# 7_07110_016_3.net
KiCad netlist of a schematic drawn in Altium Designer
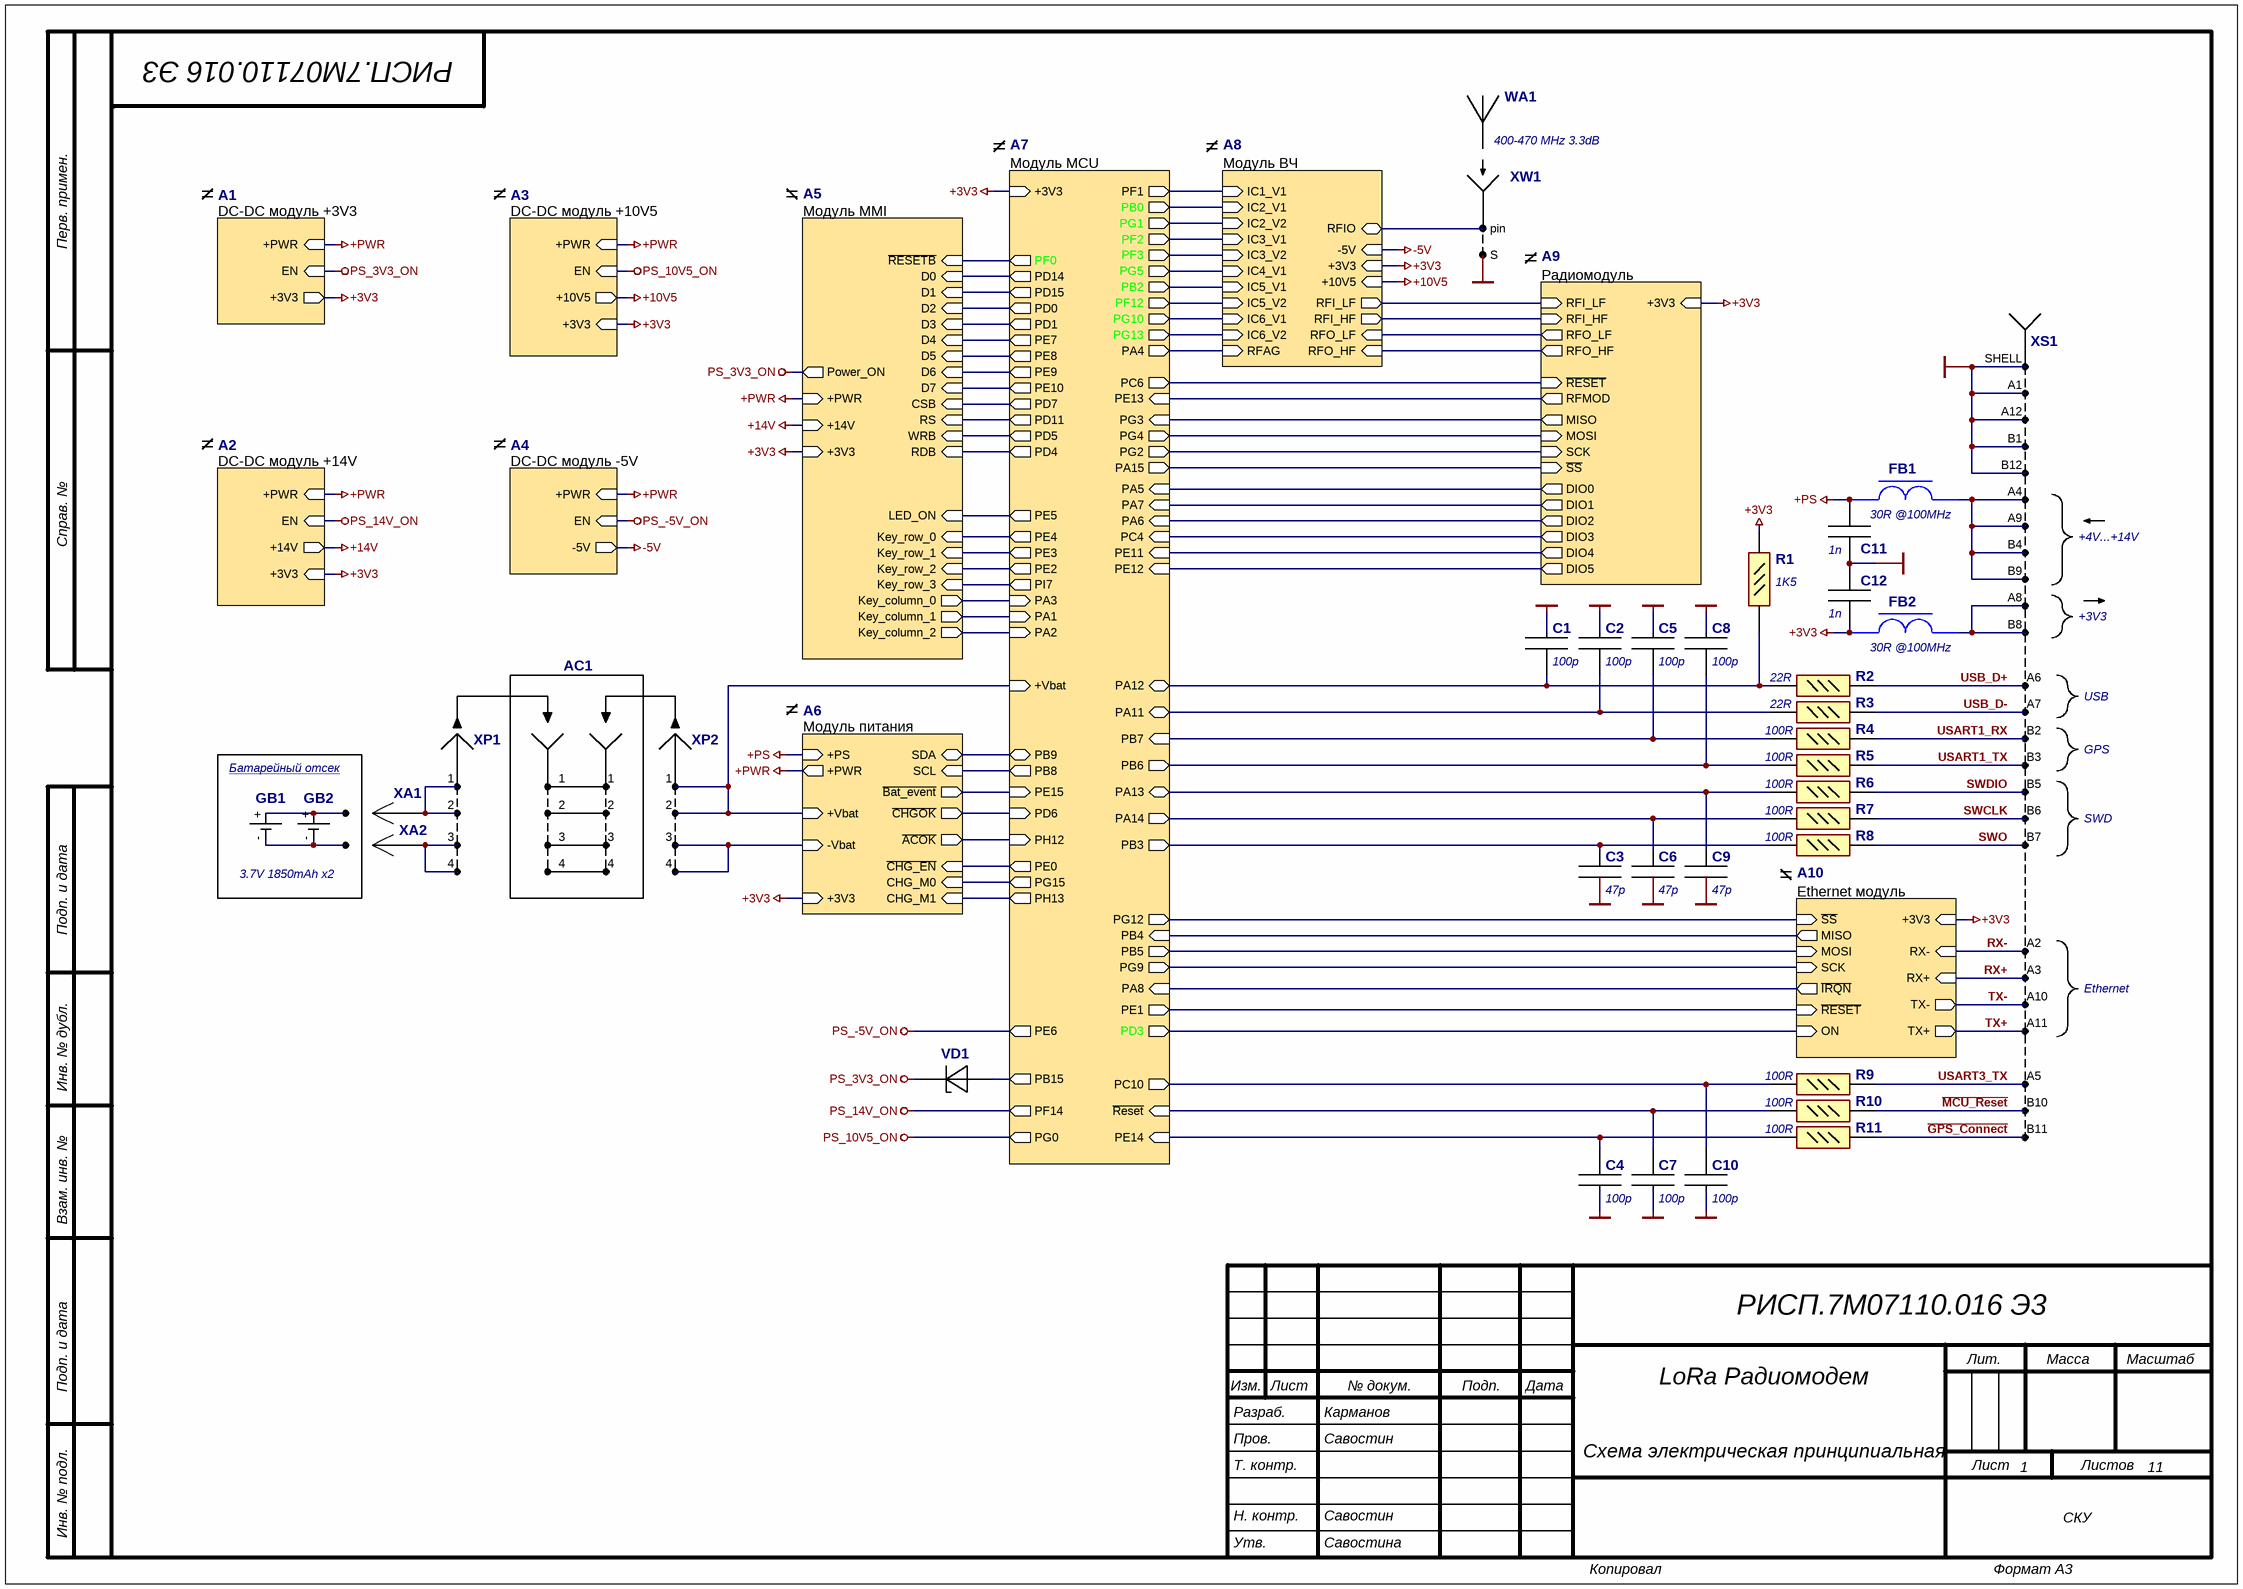
[diagram p0: РИСП.7М07110.016 Э3.SchDoc]

(export (version "E")
  (design (tool "Eeschema 10.0.6"))
  (components
    (comp (ref "AC1")
      (value "0151320401")
      (description "Cable-Assy Picolock 1.5mm Pitch 4 Wire 24AWG 100mm")
      (libsource (lib "Connectors") (part "0151320401"))
    )
    (comp (ref "C1")
      (value "100p")
      (footprint ":CAP0402 100x50x50")
      (description "CAP CER  50V C0G/NP0 0402")
      (fields (field (name "MANUFACTURER_PART_NUMBER") "GCM1555C1H101JA16D"))
      (libsource (lib "Capacitors 0402") (part "GCM1555C1H101JA16D"))
    )
    (comp (ref "C2")
      (value "100p")
      (footprint ":CAP0402 100x50x50")
      (description "CAP CER  50V C0G/NP0 0402")
      (fields (field (name "MANUFACTURER_PART_NUMBER") "GCM1555C1H101JA16D"))
      (libsource (lib "Capacitors 0402") (part "GCM1555C1H101JA16D"))
    )
    (comp (ref "C3")
      (value "47p")
      (footprint ":CAP0402 100x50x50")
      (description "CAP CER  50V C0G/NP0 0402")
      (fields (field (name "MANUFACTURER_PART_NUMBER") "GJM1555C1H470GB01D"))
      (libsource (lib "Capacitors 0402") (part "GJM1555C1H470GB01D"))
    )
    (comp (ref "C4")
      (value "100p")
      (footprint ":CAP0402 100x50x50")
      (description "CAP CER  50V C0G/NP0 0402")
      (fields (field (name "MANUFACTURER_PART_NUMBER") "GCM1555C1H101JA16D"))
      (libsource (lib "Capacitors 0402") (part "GCM1555C1H101JA16D"))
    )
    (comp (ref "C5")
      (value "100p")
      (footprint ":CAP0402 100x50x50")
      (description "CAP CER  50V C0G/NP0 0402")
      (fields (field (name "MANUFACTURER_PART_NUMBER") "GCM1555C1H101JA16D"))
      (libsource (lib "Capacitors 0402") (part "GCM1555C1H101JA16D"))
    )
    (comp (ref "C6")
      (value "47p")
      (footprint ":CAP0402 100x50x50")
      (description "CAP CER  50V C0G/NP0 0402")
      (fields (field (name "MANUFACTURER_PART_NUMBER") "GJM1555C1H470GB01D"))
      (libsource (lib "Capacitors 0402") (part "GJM1555C1H470GB01D"))
    )
    (comp (ref "C7")
      (value "100p")
      (footprint ":CAP0402 100x50x50")
      (description "CAP CER  50V C0G/NP0 0402")
      (fields (field (name "MANUFACTURER_PART_NUMBER") "GCM1555C1H101JA16D"))
      (libsource (lib "Capacitors 0402") (part "GCM1555C1H101JA16D"))
    )
    (comp (ref "C8")
      (value "100p")
      (footprint ":CAP0402 100x50x50")
      (description "CAP CER  50V C0G/NP0 0402")
      (fields (field (name "MANUFACTURER_PART_NUMBER") "GCM1555C1H101JA16D"))
      (libsource (lib "Capacitors 0402") (part "GCM1555C1H101JA16D"))
    )
    (comp (ref "C9")
      (value "47p")
      (footprint ":CAP0402 100x50x50")
      (description "CAP CER  50V C0G/NP0 0402")
      (fields (field (name "MANUFACTURER_PART_NUMBER") "GJM1555C1H470GB01D"))
      (libsource (lib "Capacitors 0402") (part "GJM1555C1H470GB01D"))
    )
    (comp (ref "C10")
      (value "100p")
      (footprint ":CAP0402 100x50x50")
      (description "CAP CER  50V C0G/NP0 0402")
      (fields (field (name "MANUFACTURER_PART_NUMBER") "GCM1555C1H101JA16D"))
      (libsource (lib "Capacitors 0402") (part "GCM1555C1H101JA16D"))
    )
    (comp (ref "C11")
      (value "1n")
      (footprint ":CAP0402 100x50x50")
      (description "±5% 50V Ceramic Capacitor C0G, NP0 0402 (1005 Metric)")
      (fields (field (name "MANUFACTURER_PART_NUMBER") "GRM1555C1H102JA01J"))
      (libsource (lib "Capacitors 0402") (part "GRM1555C1H102JA01J"))
    )
    (comp (ref "C12")
      (value "1n")
      (footprint ":CAP0402 100x50x50")
      (description "±5% 50V Ceramic Capacitor C0G, NP0 0402 (1005 Metric)")
      (fields (field (name "MANUFACTURER_PART_NUMBER") "GRM1555C1H102JA01J"))
      (libsource (lib "Capacitors 0402") (part "GRM1555C1H102JA01J"))
    )
    (comp (ref "FB1")
      (value "30R @100MHz")
      (footprint ":FER BLM18SP300SN1D")
      (description "30 Ohms @ 100MHz 1 Power Line Ferrite Bead 0603 (1608 Metric) 6A 8mOhm")
      (fields
        (field (name "MANUFACTURER_PART_NUMBER") "BLM18SP300SN1D")
        (field (name "MOUSER PART NUMBER") "81-BLM18SP300SN1D")
      )
      (libsource (lib "Ferrite Bead") (part "BLM18SP300SN1D"))
    )
    (comp (ref "FB2")
      (value "30R @100MHz")
      (footprint ":FER BLM18SP300SN1D")
      (description "30 Ohms @ 100MHz 1 Power Line Ferrite Bead 0603 (1608 Metric) 6A 8mOhm")
      (fields
        (field (name "MANUFACTURER_PART_NUMBER") "BLM18SP300SN1D")
        (field (name "MOUSER PART NUMBER") "81-BLM18SP300SN1D")
      )
      (libsource (lib "Ferrite Bead") (part "BLM18SP300SN1D"))
    )
    (comp (ref "GB1")
      (value "3.7V 1850mAh")
      (description "Battery Li-po 3.7V 1850mAh 10х34х50")
      (fields (field (name "MANUFACTURER_PART_NUMBER") "LP-1850-103450UN"))
      (libsource (lib "Other") (part "LP-1850-103450UN"))
    )
    (comp (ref "GB2")
      (value "3.7V 1850mAh")
      (description "Battery Li-po 3.7V 1850mAh 10х34х50")
      (fields (field (name "MANUFACTURER_PART_NUMBER") "LP-1850-103450UN"))
      (libsource (lib "Other") (part "LP-1850-103450UN"))
    )
    (comp (ref "R1")
      (value "RC0402FR-07")
      (footprint ":RES0402")
      (fields (field (name "MANUFACTURER_PART_NUMBER (PART 2: VALUE)") "1K5"))
      (libsource (lib "") (part "RC0402FR-07_1"))
    )
    (comp (ref "R2")
      (value "RC0402FR-07")
      (footprint ":RES0402")
      (fields (field (name "MANUFACTURER_PART_NUMBER (PART 2: VALUE)") "22R"))
      (libsource (lib "Resistors 0402") (part "RC0402FR-07"))
    )
    (comp (ref "R3")
      (value "RC0402FR-07")
      (footprint ":RES0402")
      (fields (field (name "MANUFACTURER_PART_NUMBER (PART 2: VALUE)") "22R"))
      (libsource (lib "Resistors 0402") (part "RC0402FR-07"))
    )
    (comp (ref "R4")
      (value "RC0402FR-07")
      (footprint ":RES0402")
      (fields (field (name "MANUFACTURER_PART_NUMBER (PART 2: VALUE)") "100R"))
      (libsource (lib "Resistors 0402") (part "RC0402FR-07"))
    )
    (comp (ref "R5")
      (value "RC0402FR-07")
      (footprint ":RES0402")
      (fields (field (name "MANUFACTURER_PART_NUMBER (PART 2: VALUE)") "100R"))
      (libsource (lib "Resistors 0402") (part "RC0402FR-07"))
    )
    (comp (ref "R6")
      (value "RC0402FR-07")
      (footprint ":RES0402")
      (fields (field (name "MANUFACTURER_PART_NUMBER (PART 2: VALUE)") "100R"))
      (libsource (lib "Resistors 0402") (part "RC0402FR-07"))
    )
    (comp (ref "R7")
      (value "RC0402FR-07")
      (footprint ":RES0402")
      (fields (field (name "MANUFACTURER_PART_NUMBER (PART 2: VALUE)") "100R"))
      (libsource (lib "Resistors 0402") (part "RC0402FR-07"))
    )
    (comp (ref "R8")
      (value "RC0402FR-07")
      (footprint ":RES0402")
      (fields (field (name "MANUFACTURER_PART_NUMBER (PART 2: VALUE)") "100R"))
      (libsource (lib "Resistors 0402") (part "RC0402FR-07"))
    )
    (comp (ref "R9")
      (value "RC0402FR-07")
      (footprint ":RES0402")
      (fields (field (name "MANUFACTURER_PART_NUMBER (PART 2: VALUE)") "100R"))
      (libsource (lib "Resistors 0402") (part "RC0402FR-07"))
    )
    (comp (ref "R10")
      (value "RC0402FR-07")
      (footprint ":RES0402")
      (fields (field (name "MANUFACTURER_PART_NUMBER (PART 2: VALUE)") "100R"))
      (libsource (lib "Resistors 0402") (part "RC0402FR-07"))
    )
    (comp (ref "R11")
      (value "RC0402FR-07")
      (footprint ":RES0402")
      (fields (field (name "MANUFACTURER_PART_NUMBER (PART 2: VALUE)") "100R"))
      (libsource (lib "Resistors 0402") (part "RC0402FR-07"))
    )
    (comp (ref "VD1")
      (value "30V 0.1A")
      (footprint ":DIODE SOD-923F")
      (description "Diodes Schottky 0402 30V 0.1A")
      (fields
        (field (name "MANUFACTURER_PART_NUMBER") "CDBQR0130R")
        (field (name "MOUSER PART NUMBER") "750-CDBQR0130R")
      )
      (libsource (lib "Diodes 0402") (part "CDBQR0130R"))
    )
    (comp (ref "WA1")
      (value "ANT-433-CW-QW-SMA-male")
      (description "Antenna 400-470MHz 3.3dB SMA male")
      (fields (field (name "SHORT DESCRIPTION") "400-470 MHz 3.3dB"))
      (libsource (lib "Antennas") (part "ANT-433-CW-QW-SMA-male"))
    )
    (comp (ref "X1")
      (value "Big Circle Pad")
      (description "Большая круглая контактная площадка")
      (libsource (lib "Connectors") (part "Big Circle Pad"))
    )
    (comp (ref "X2")
      (value "Big Circle Pad")
      (description "Большая круглая контактная площадка")
      (libsource (lib "Connectors") (part "Big Circle Pad"))
    )
    (comp (ref "XA1")
      (value "0861-0-15-20-82-14-11-0")
      (description "Контакт пружинный 9A 10mm")
      (libsource (lib "Connectors") (part "0861-0-15-20-82-14-11-0"))
    )
    (comp (ref "XA2")
      (value "0861-0-15-20-82-14-11-0")
      (description "Контакт пружинный 9A 10mm")
      (libsource (lib "Connectors") (part "0861-0-15-20-82-14-11-0"))
    )
    (comp (ref "XP1")
      (value "5040500491")
      (footprint ":CON 5040500491")
      (description "Picolock 1.5mm Pitch Male 4-pin")
      (libsource (lib "Connectors") (part "5040500491"))
    )
    (comp (ref "XP2")
      (value "5040500491")
      (footprint ":CON 5040500491")
      (description "Picolock 1.5mm Pitch Male 4-pin")
      (libsource (lib "Connectors") (part "5040500491"))
    )
    (comp (ref "XS1")
      (value "UJ31-CH-3-MSMT-TR-67")
      (footprint ":CON TYPE-C UJ31-CH-3-MSMT-TR-67")
      (description "type C IP67 with ruber O ring")
      (libsource (lib "Connectors") (part "UJ31-CH-3-MSMT-TR-67"))
    )
    (comp (ref "XW1")
      (value "132371")
      (footprint ":CON 132371")
      (description "RF SMA Connectors 50Ohm")
      (libsource (lib "Connectors") (part "132371"))
    )
  )
  (nets
    (net (code "1") (name "+3V3") (class "Default")
      (node (ref "C12") (pin "2") (pinfunction "2_2") (pintype "passive"))
      (node (ref "FB2") (pin "1") (pinfunction "1_1") (pintype "passive"))
      (node (ref "R1") (pin "2") (pinfunction "2_2") (pintype "passive"))
    )
    (net (code "4") (name "+PS") (class "Default")
      (node (ref "C11") (pin "1") (pinfunction "1_1") (pintype "passive"))
      (node (ref "FB1") (pin "1") (pinfunction "1_1") (pintype "passive"))
    )
    (net (code "7") (name "/+Vbat") (class "Default")
      (node (ref "XP2") (pin "1") (pinfunction "1_1") (pintype "passive"))
      (node (ref "XP2") (pin "2") (pinfunction "2_2") (pintype "passive"))
    )
    (net (code "8") (name "/-Vbat") (class "Default")
      (node (ref "XP2") (pin "3") (pinfunction "3_3") (pintype "passive"))
      (node (ref "XP2") (pin "4") (pinfunction "4_4") (pintype "passive"))
    )
    (net (code "21") (name "/PA11") (class "Default")
      (node (ref "C2") (pin "1") (pinfunction "1_1") (pintype "passive"))
      (node (ref "R3") (pin "1") (pinfunction "1_1") (pintype "passive"))
    )
    (net (code "22") (name "/PA12") (class "Default")
      (node (ref "C1") (pin "1") (pinfunction "1_1") (pintype "passive"))
      (node (ref "R1") (pin "1") (pinfunction "1_1") (pintype "passive"))
      (node (ref "R2") (pin "1") (pinfunction "1_1") (pintype "passive"))
    )
    (net (code "23") (name "/PA13") (class "Default")
      (node (ref "C9") (pin "1") (pinfunction "1_1") (pintype "passive"))
      (node (ref "R6") (pin "1") (pinfunction "1_1") (pintype "passive"))
    )
    (net (code "24") (name "/PA14") (class "Default")
      (node (ref "C6") (pin "1") (pinfunction "1_1") (pintype "passive"))
      (node (ref "R7") (pin "1") (pinfunction "1_1") (pintype "passive"))
    )
    (net (code "28") (name "/PB3") (class "Default")
      (node (ref "C3") (pin "1") (pinfunction "1_1") (pintype "passive"))
      (node (ref "R8") (pin "1") (pinfunction "1_1") (pintype "passive"))
    )
    (net (code "30") (name "/PB6") (class "Default")
      (node (ref "C8") (pin "1") (pinfunction "1_1") (pintype "passive"))
      (node (ref "R5") (pin "1") (pinfunction "1_1") (pintype "passive"))
    )
    (net (code "31") (name "/PB7") (class "Default")
      (node (ref "C5") (pin "1") (pinfunction "1_1") (pintype "passive"))
      (node (ref "R4") (pin "1") (pinfunction "1_1") (pintype "passive"))
    )
    (net (code "34") (name "/PB15") (class "Default")
      (node (ref "VD1") (pin "2") (pinfunction "A_2") (pintype "passive"))
    )
    (net (code "36") (name "/PC10") (class "Default")
      (node (ref "C10") (pin "1") (pinfunction "1_1") (pintype "passive"))
      (node (ref "R9") (pin "1") (pinfunction "1_1") (pintype "passive"))
    )
    (net (code "56") (name "/PE14") (class "Default")
      (node (ref "C4") (pin "1") (pinfunction "1_1") (pintype "passive"))
      (node (ref "R11") (pin "1") (pinfunction "1_1") (pintype "passive"))
    )
    (net (code "73") (name "/RFIO") (class "Default")
      (node (ref "XW1") (pin "1") (pinfunction "pin_1") (pintype "passive"))
    )
    (net (code "79") (name "/RX+") (class "Default")
      (node (ref "XS1") (pin "A3") (pinfunction "SSTXN1_A3") (pintype "passive"))
    )
    (net (code "80") (name "/RX-") (class "Default")
      (node (ref "XS1") (pin "A2") (pinfunction "SSTXP1_A2") (pintype "passive"))
    )
    (net (code "81") (name "/SWCLK") (class "Default")
      (node (ref "R7") (pin "2") (pinfunction "2_2") (pintype "passive"))
      (node (ref "XS1") (pin "B6") (pinfunction "DP2_B6") (pintype "passive"))
    )
    (net (code "82") (name "/SWDIO") (class "Default")
      (node (ref "R6") (pin "2") (pinfunction "2_2") (pintype "passive"))
      (node (ref "XS1") (pin "B5") (pinfunction "CC2_B5") (pintype "passive"))
    )
    (net (code "83") (name "/SWO") (class "Default")
      (node (ref "R8") (pin "2") (pinfunction "2_2") (pintype "passive"))
      (node (ref "XS1") (pin "B7") (pinfunction "DN2_B7") (pintype "passive"))
    )
    (net (code "84") (name "/TX+") (class "Default")
      (node (ref "XS1") (pin "A11") (pinfunction "SSRXP2_A11") (pintype "passive"))
    )
    (net (code "85") (name "/TX-") (class "Default")
      (node (ref "XS1") (pin "A10") (pinfunction "SSRXN2_A10") (pintype "passive"))
    )
    (net (code "86") (name "/USART1_RX") (class "Default")
      (node (ref "R4") (pin "2") (pinfunction "2_2") (pintype "passive"))
      (node (ref "XS1") (pin "B2") (pinfunction "SSTXP2_B2") (pintype "passive"))
    )
    (net (code "87") (name "/USART1_TX") (class "Default")
      (node (ref "R5") (pin "2") (pinfunction "2_2") (pintype "passive"))
      (node (ref "XS1") (pin "B3") (pinfunction "SSTXN2_B3") (pintype "passive"))
    )
    (net (code "88") (name "/USART3_TX") (class "Default")
      (node (ref "R9") (pin "2") (pinfunction "2_2") (pintype "passive"))
      (node (ref "XS1") (pin "A5") (pinfunction "CC1_A5") (pintype "passive"))
    )
    (net (code "89") (name "/USB_D+") (class "Default")
      (node (ref "R2") (pin "2") (pinfunction "2_2") (pintype "passive"))
      (node (ref "XS1") (pin "A6") (pinfunction "DP1_A6") (pintype "passive"))
    )
    (net (code "90") (name "/USB_D-") (class "Default")
      (node (ref "R3") (pin "2") (pinfunction "2_2") (pintype "passive"))
      (node (ref "XS1") (pin "A7") (pinfunction "DN1_A7") (pintype "passive"))
    )
    (net (code "94") (name "/~{GPS_Connect}") (class "Default")
      (node (ref "R11") (pin "2") (pinfunction "2_2") (pintype "passive"))
      (node (ref "XS1") (pin "B11") (pinfunction "SSRXP1_B11") (pintype "passive"))
    )
    (net (code "96") (name "/~{MCU_Reset}") (class "Default")
      (node (ref "R10") (pin "2") (pinfunction "2_2") (pintype "passive"))
      (node (ref "XS1") (pin "B10") (pinfunction "SSRXN1_B10") (pintype "passive"))
    )
    (net (code "97") (name "/~{Reset}") (class "Default")
      (node (ref "C7") (pin "1") (pinfunction "1_1") (pintype "passive"))
      (node (ref "R10") (pin "1") (pinfunction "1_1") (pintype "passive"))
    )
    (net (code "98") (name "GND") (class "Default")
      (node (ref "C1") (pin "2") (pinfunction "2_2") (pintype "passive"))
      (node (ref "C10") (pin "2") (pinfunction "2_2") (pintype "passive"))
      (node (ref "C11") (pin "2") (pinfunction "2_2") (pintype "passive"))
      (node (ref "C12") (pin "1") (pinfunction "1_1") (pintype "passive"))
      (node (ref "C2") (pin "2") (pinfunction "2_2") (pintype "passive"))
      (node (ref "C3") (pin "2") (pinfunction "2_2") (pintype "passive"))
      (node (ref "C4") (pin "2") (pinfunction "2_2") (pintype "passive"))
      (node (ref "C5") (pin "2") (pinfunction "2_2") (pintype "passive"))
      (node (ref "C6") (pin "2") (pinfunction "2_2") (pintype "passive"))
      (node (ref "C7") (pin "2") (pinfunction "2_2") (pintype "passive"))
      (node (ref "C8") (pin "2") (pinfunction "2_2") (pintype "passive"))
      (node (ref "C9") (pin "2") (pinfunction "2_2") (pintype "passive"))
      (node (ref "XS1") (pin "A1") (pinfunction "GND_1_A1") (pintype "passive"))
      (node (ref "XS1") (pin "A12") (pinfunction "GND_2_A12") (pintype "passive"))
      (node (ref "XS1") (pin "B1") (pinfunction "GND_3_B1") (pintype "passive"))
      (node (ref "XS1") (pin "B12") (pinfunction "GND_4_B12") (pintype "passive"))
      (node (ref "XS1") (pin "SHELL") (pinfunction "SHELL_SHELL") (pintype "passive"))
      (node (ref "XW1") (pin "2") (pinfunction "S_2") (pintype "passive"))
    )
    (net (code "99") (name "Net-(GB1-black)") (class "Default")
      (node (ref "GB1") (pin "-") (pinfunction "black_-") (pintype "passive"))
      (node (ref "GB2") (pin "-") (pinfunction "black_-") (pintype "passive"))
      (node (ref "X2") (pin "1") (pinfunction "1_1") (pintype "passive"))
    )
    (net (code "100") (name "Net-(GB1-red)") (class "Default")
      (node (ref "GB1") (pin "+") (pinfunction "red_+") (pintype "passive"))
      (node (ref "GB2") (pin "+") (pinfunction "red_+") (pintype "passive"))
      (node (ref "X1") (pin "1") (pinfunction "1_1") (pintype "passive"))
    )
    (net (code "101") (name "Net-(XA1-Pad1)") (class "Default")
      (node (ref "XA1") (pin "1") (pinfunction "1_1") (pintype "passive"))
      (node (ref "XP1") (pin "1") (pinfunction "1_1") (pintype "passive"))
      (node (ref "XP1") (pin "2") (pinfunction "2_2") (pintype "passive"))
    )
    (net (code "102") (name "Net-(XA2-Pad1)") (class "Default")
      (node (ref "XA2") (pin "1") (pinfunction "1_1") (pintype "passive"))
      (node (ref "XP1") (pin "3") (pinfunction "3_3") (pintype "passive"))
      (node (ref "XP1") (pin "4") (pinfunction "4_4") (pintype "passive"))
    )
    (net (code "103") (name "Net-(XS1-SBU1)") (class "Default")
      (node (ref "FB2") (pin "2") (pinfunction "2_2") (pintype "passive"))
      (node (ref "XS1") (pin "A8") (pinfunction "SBU1_A8") (pintype "passive"))
      (node (ref "XS1") (pin "B8") (pinfunction "SBU2_B8") (pintype "passive"))
    )
    (net (code "104") (name "Net-(XS1-VBUS_1)") (class "Default")
      (node (ref "FB1") (pin "2") (pinfunction "2_2") (pintype "passive"))
      (node (ref "XS1") (pin "A4") (pinfunction "VBUS_1_A4") (pintype "passive"))
      (node (ref "XS1") (pin "A9") (pinfunction "VBUS_2_A9") (pintype "passive"))
      (node (ref "XS1") (pin "B4") (pinfunction "VBUS_3_B4") (pintype "passive"))
      (node (ref "XS1") (pin "B9") (pinfunction "VBUS_4_B9") (pintype "passive"))
    )
    (net (code "106") (name "PS_3V3_ON") (class "Default")
      (node (ref "VD1") (pin "1") (pinfunction "K_1") (pintype "passive"))
    )
    (net (code "109") (name "unconnected-(AC1-Pad1)") (class "Default")
      (node (ref "AC1") (pin "1") (pinfunction "1_1") (pintype "passive"))
    )
    (net (code "110") (name "unconnected-(AC1-Pad2)") (class "Default")
      (node (ref "AC1") (pin "2") (pinfunction "2_2") (pintype "passive"))
    )
    (net (code "111") (name "unconnected-(AC1-Pad3)") (class "Default")
      (node (ref "AC1") (pin "3") (pinfunction "3_3") (pintype "passive"))
    )
    (net (code "112") (name "unconnected-(AC1-Pad4)") (class "Default")
      (node (ref "AC1") (pin "4") (pinfunction "4_4") (pintype "passive"))
    )
  )
)
